# Sense_2_Signal_Isolation.net
KiCad netlist of a schematic drawn in Altium Designer
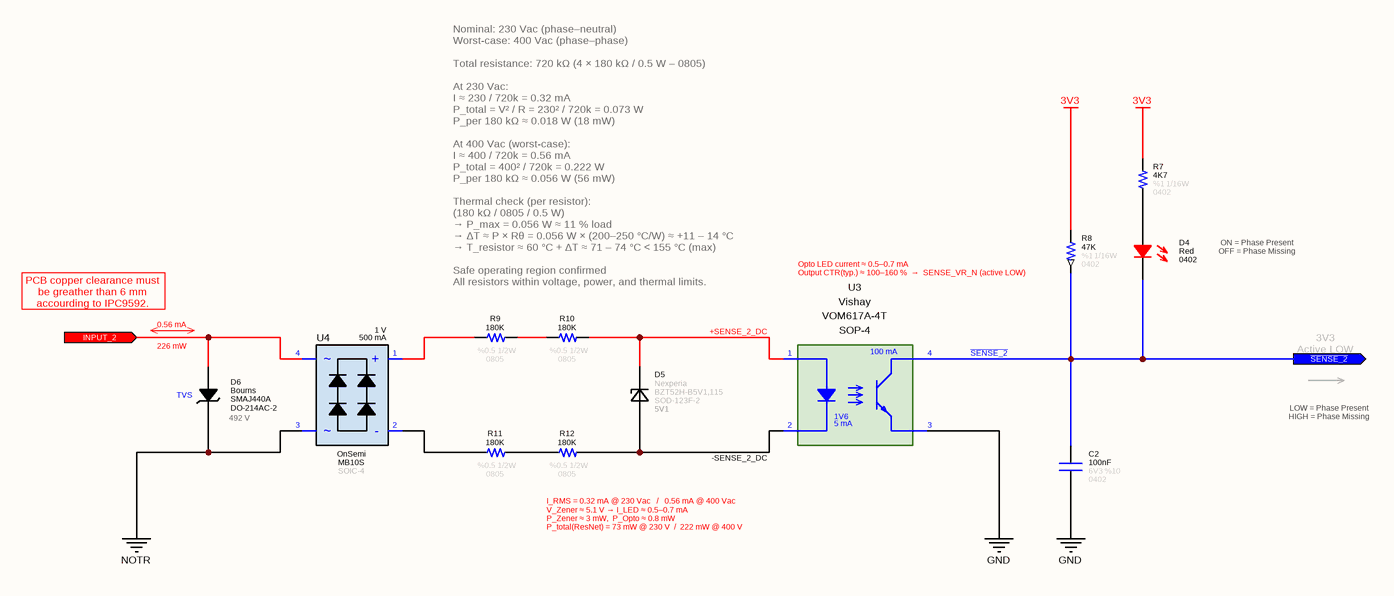
[diagram p0: Sense 2 Signal Isolation.SchDoc]

(export (version "E")
  (design (tool "Eeschema 10.0.6"))
  (components
    (comp (ref "C2")
      (value "100nF")
      (footprint "CAPACITOR_0402")
      (description "Capacitor (MLCC) - 100nF / 6V3 / 0402")
      (fields
        (field (name "MANUFACTURER PART NUMBER") "04026D104KAT4A")
        (field (name "TOLERANCE") "%10")
        (field (name "VOLTAGE") "6V3")
        (field (name "CASE") "0402")
        (field (name "Comment") "Capacitor - 100nF [0402] (MLCC)")
      )
      (libsource (lib "Akkoyun") (part "Capacitor - 100nF [0402-6V3]"))
    )
    (comp (ref "D4")
      (value "SMD LED (Red)")
      (footprint "LED_0402")
      (description "Standard LEDs - SMD MINI-MOLD ULTRA COMPACT RED")
      (fields
        (field (name "MANUFACTURER PART NUMBER") "SML-P12VTT86R")
        (field (name "CASE") "0402")
        (field (name "COLOR") "Red")
      )
      (libsource (lib "Akkoyun") (part "Diode - LED (0402-Red)"))
    )
    (comp (ref "D5")
      (value "BZT52H-B5V1,115")
      (footprint "SOD-123F-2")
      (description "Zener Diodes BZT52H-B5V1/SOD123F/SOD2")
      (fields
        (field (name "ZENER VOLTAGE") "5V1")
        (field (name "MANUFACTURER NAME") "Nexperia")
        (field (name "MANUFACTURER PART NUMBER") "BZT52H-B5V1,115")
        (field (name "CASE") "SOD-123F-2")
      )
      (libsource (lib "Akkoyun") (part "Diode - BZT52H-B5V1,115"))
    )
    (comp (ref "D6")
      (value "SMAJ440A")
      (footprint "DO-220AA-2")
      (description "ESD Protection Diodes / TVS Diodes 440volts 1uA .6 Amps Uni-Dir")
      (fields
        (field (name "BREAKDOWN VOLTAGE") "492 V")
        (field (name "MANUFACTURER NAME") "Bourns")
        (field (name "MANUFACTURER PART NUMBER") "SMAJ440A")
        (field (name "CASE") "DO-214AC-2")
      )
      (libsource (lib "Akkoyun") (part "Diode - SMAJ440A (TVS)"))
    )
    (comp (ref "R7")
      (value "4K7")
      (footprint "RESISTOR_0402")
      (description "Thick Film Resistors - SMD 1/16 W 4.7 KOhm 1%")
      (fields
        (field (name "MANUFACTURER PART NUMBER") "CRCW04024K70FKED")
        (field (name "TOLERANCE") "%1")
        (field (name "CASE") "0402")
        (field (name "POWER") "1/16W")
        (field (name "Comment") "4K7 - 0402 - %1 - 1/16W")
      )
      (libsource (lib "Akkoyun") (part "Resistor - 4K7 [0402]"))
    )
    (comp (ref "R8")
      (value "47K")
      (footprint "RESISTOR_0402")
      (description "Thick Film Resistors - SMD 1/16 W 47 KOhm 1%")
      (fields
        (field (name "MANUFACTURER PART NUMBER") "CRCW040247K0FKED")
        (field (name "TOLERANCE") "%1")
        (field (name "CASE") "0402")
        (field (name "POWER") "1/16W")
        (field (name "Comment") "47K - 0402 - %1 - 1/16W")
      )
      (libsource (lib "Akkoyun") (part "Resistor - 47K [0402]"))
    )
    (comp (ref "R9")
      (value "180K")
      (footprint "RESISTOR_0805")
      (description "Thick Film Resistors - SMD 0805 180Kohms 0.5W 0.5% AEC-Q200")
      (fields
        (field (name "MANUFACTURER PART NUMBER") "ERJ-P06D1803V")
        (field (name "TOLERANCE") "%0.5")
        (field (name "CASE") "0805")
        (field (name "POWER") "1/2W")
        (field (name "Comment") "180K - 0805 - %0.5 - 1/2W")
      )
      (libsource (lib "Akkoyun") (part "Resistor - 180K [0805]"))
    )
    (comp (ref "R10")
      (value "180K")
      (footprint "RESISTOR_0805")
      (description "Thick Film Resistors - SMD 0805 180Kohms 0.5W 0.5% AEC-Q200")
      (fields
        (field (name "MANUFACTURER PART NUMBER") "ERJ-P06D1803V")
        (field (name "TOLERANCE") "%0.5")
        (field (name "CASE") "0805")
        (field (name "POWER") "1/2W")
        (field (name "Comment") "180K - 0805 - %0.5 - 1/2W")
      )
      (libsource (lib "Akkoyun") (part "Resistor - 180K [0805]"))
    )
    (comp (ref "R11")
      (value "180K")
      (footprint "RESISTOR_0805")
      (description "Thick Film Resistors - SMD 0805 180Kohms 0.5W 0.5% AEC-Q200")
      (fields
        (field (name "MANUFACTURER PART NUMBER") "ERJ-P06D1803V")
        (field (name "TOLERANCE") "%0.5")
        (field (name "CASE") "0805")
        (field (name "POWER") "1/2W")
        (field (name "Comment") "180K - 0805 - %0.5 - 1/2W")
      )
      (libsource (lib "Akkoyun") (part "Resistor - 180K [0805]"))
    )
    (comp (ref "R12")
      (value "180K")
      (footprint "RESISTOR_0805")
      (description "Thick Film Resistors - SMD 0805 180Kohms 0.5W 0.5% AEC-Q200")
      (fields
        (field (name "MANUFACTURER PART NUMBER") "ERJ-P06D1803V")
        (field (name "TOLERANCE") "%0.5")
        (field (name "CASE") "0805")
        (field (name "POWER") "1/2W")
        (field (name "Comment") "180K - 0805 - %0.5 - 1/2W")
      )
      (libsource (lib "Akkoyun") (part "Resistor - 180K [0805]"))
    )
    (comp (ref "U3")
      (value "VOM617A-4T")
      (footprint "SOP-4V2")
      (description "Transistor Output Optocouplers Phototransistor Out CTR 160-320% 5mA")
      (fields
        (field (name "MANUFACTURER PART NUMBER") "VOM617A-4T")
        (field (name "MANUFACTURER NAME") "Vishay")
        (field (name "CASE") "SOP-4")
        (field (name "IF - FORWARD CURRENT") "5 mA")
        (field (name "VF - FORWARD VOLTAGE") "1V6")
        (field (name "MAXIMUM COLLECTOR CURRENT") "100 mA")
      )
      (libsource (lib "Akkoyun") (part "IC - VOM617A"))
    )
    (comp (ref "U4")
      (value "LTV-846S")
      (footprint "SOIC-4")
      (description "Transistor Output Optocouplers Optocplr Phototrans 4-Channel")
      (fields
        (field (name "IF - FORWARD CURRENT") "500 mA")
        (field (name "VF - FORWARD VOLTAGE") "1 V")
        (field (name "MANUFACTURER NAME") "OnSemi")
        (field (name "MANUFACTURER PART NUMBER") "MB10S")
        (field (name "CASE") "SOIC-4")
      )
      (libsource (lib "Akkoyun") (part "IC - MB10S"))
    )
  )
  (nets
    (net (code "1") (name "/+SENSE_2_DC") (class "Default")
      (node (ref "D5") (pin "1") (pinfunction "Cathode_1") (pintype "passive"))
      (node (ref "R10") (pin "1") (pinfunction "1_1") (pintype "passive"))
      (node (ref "U3") (pin "1") (pinfunction "LED_Anode_1") (pintype "passive"))
    )
    (net (code "2") (name "/-SENSE_2_DC") (class "Default")
      (node (ref "D5") (pin "2") (pinfunction "Anode_2") (pintype "passive"))
      (node (ref "R12") (pin "1") (pinfunction "1_1") (pintype "passive"))
      (node (ref "U3") (pin "2") (pinfunction "LED_Cathode_2") (pintype "passive"))
    )
    (net (code "3") (name "/INPUT_2") (class "Default")
      (node (ref "D6") (pin "1") (pinfunction "Anode_1") (pintype "passive"))
      (node (ref "U4") (pin "4") (pinfunction "~_4") (pintype "passive"))
    )
    (net (code "4") (name "/~{SENSE_2}") (class "Default")
      (node (ref "C2") (pin "2") (pinfunction "2_2") (pintype "passive"))
      (node (ref "D4") (pin "1") (pinfunction "1_1") (pintype "passive"))
      (node (ref "R8") (pin "1") (pinfunction "1_1") (pintype "output"))
      (node (ref "U3") (pin "4") (pinfunction "Collector_4") (pintype "passive"))
    )
    (net (code "5") (name "3V3") (class "Default")
      (node (ref "R7") (pin "2") (pinfunction "2_2") (pintype "passive"))
      (node (ref "R8") (pin "2") (pinfunction "2_2") (pintype "passive"))
    )
    (net (code "6") (name "GND") (class "Default")
      (node (ref "C2") (pin "1") (pinfunction "1_1") (pintype "passive"))
      (node (ref "U3") (pin "3") (pinfunction "Emiter_3") (pintype "passive"))
    )
    (net (code "7") (name "NOTR") (class "Default")
      (node (ref "D6") (pin "2") (pinfunction "Cathode_2") (pintype "passive"))
      (node (ref "U4") (pin "3") (pinfunction "~_3") (pintype "passive"))
    )
    (net (code "8") (name "Net-(D4-Pad2)") (class "Default")
      (node (ref "D4") (pin "2") (pinfunction "2_2") (pintype "passive"))
      (node (ref "R7") (pin "1") (pinfunction "1_1") (pintype "passive"))
    )
    (net (code "9") (name "Net-(R10-Pad2)") (class "Default")
      (node (ref "R10") (pin "2") (pinfunction "2_2") (pintype "passive"))
      (node (ref "R9") (pin "1") (pinfunction "1_1") (pintype "passive"))
    )
    (net (code "10") (name "Net-(R11-Pad1)") (class "Default")
      (node (ref "R11") (pin "1") (pinfunction "1_1") (pintype "passive"))
      (node (ref "R12") (pin "2") (pinfunction "2_2") (pintype "passive"))
    )
    (net (code "11") (name "Net-(U4-+)") (class "Default")
      (node (ref "R9") (pin "2") (pinfunction "2_2") (pintype "passive"))
      (node (ref "U4") (pin "1") (pinfunction "+_1") (pintype "passive"))
    )
    (net (code "12") (name "Net-(U4--)") (class "Default")
      (node (ref "R11") (pin "2") (pinfunction "2_2") (pintype "passive"))
      (node (ref "U4") (pin "2") (pinfunction "-_2") (pintype "passive"))
    )
  )
)
